# 04-PCIe_JTAG.net
KiCad netlist of a schematic drawn in Altium Designer
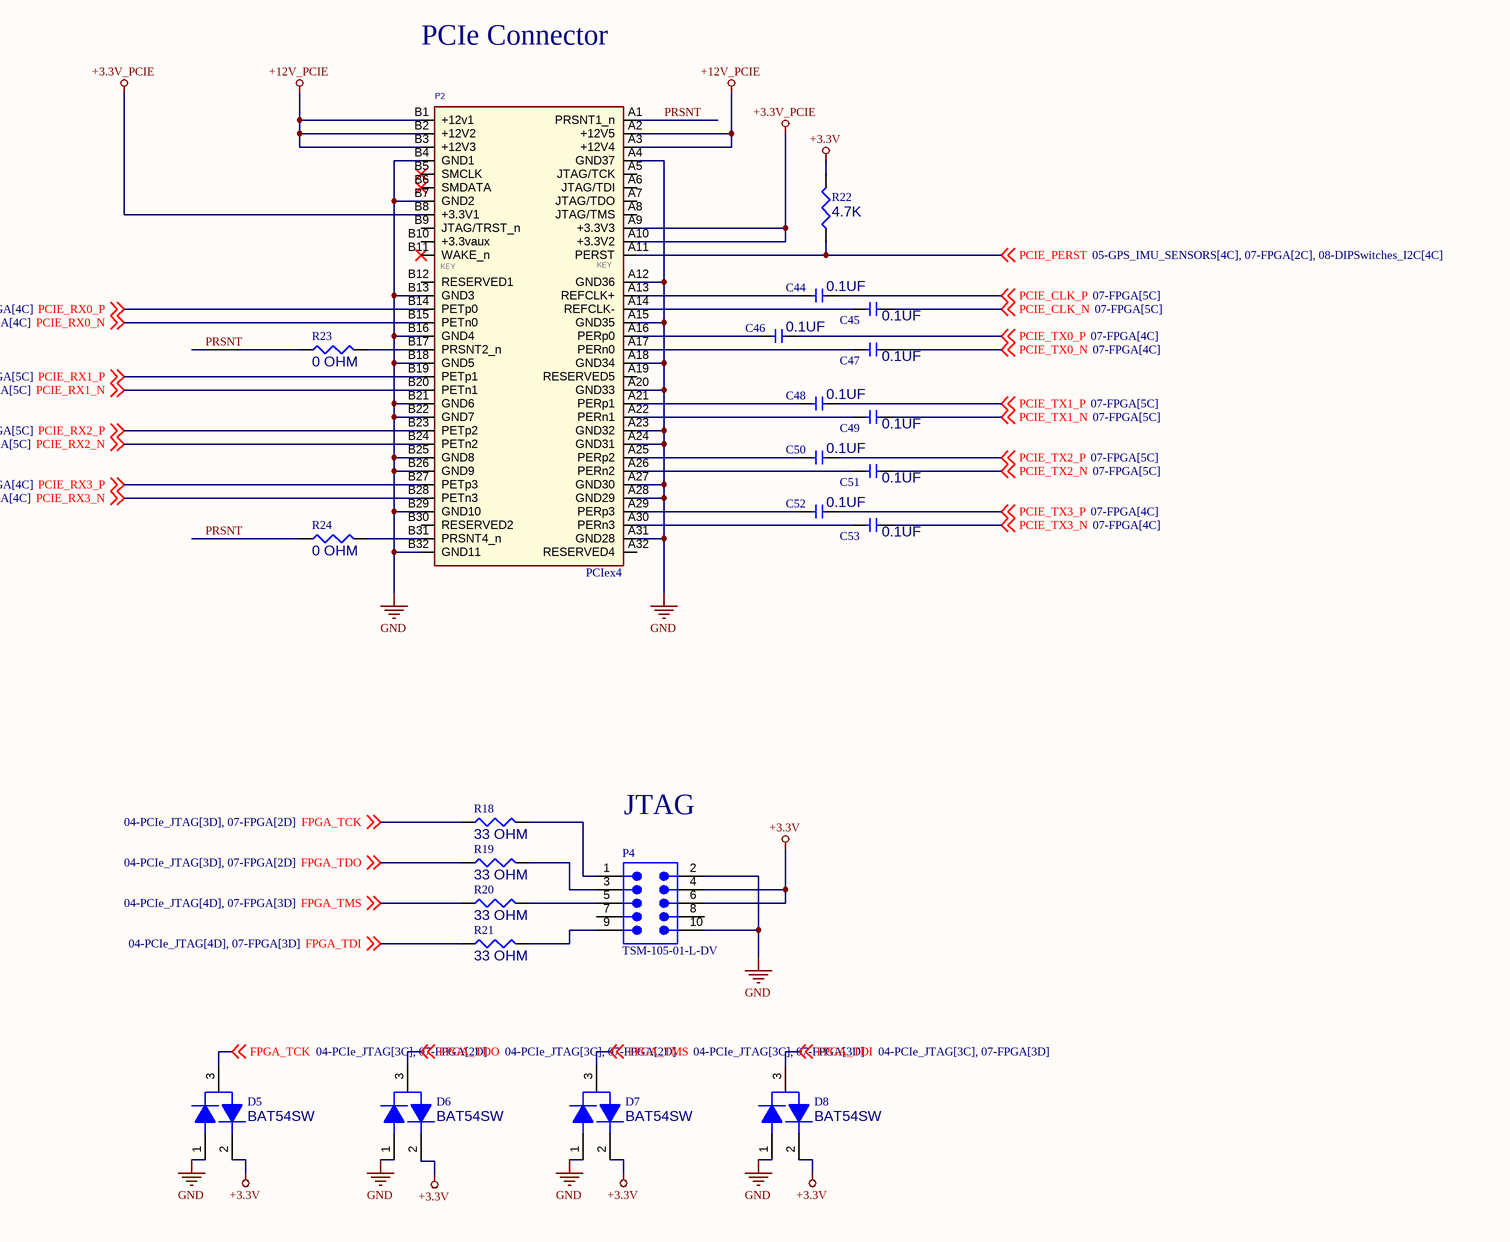
[diagram p0: 04-PCIe_JTAG.SchDoc]

(export (version "E")
  (design (tool "Eeschema 10.0.6"))
  (components
    (comp (ref "C44")
      (value "0.1UF")
      (footprint "CAPC1005X06N")
      (description "CAP, CER, 0.1UF, 50V, 10%, X7R, AEC-Q200, 0402")
      (fields
        (field (name "MFG PART NUM") "CGA2B3X7R1H104K050BB")
        (field (name "VALENTIUM PART NUM") "<VALENTIUM>")
      )
      (libsource (lib "Capacitors") (part "CAP_0402_0.1UF_50V"))
    )
    (comp (ref "C45")
      (value "0.1UF")
      (footprint "CAPC1005X06N")
      (description "CAP, CER, 0.1UF, 50V, 10%, X7R, AEC-Q200, 0402")
      (fields
        (field (name "MFG PART NUM") "CGA2B3X7R1H104K050BB")
        (field (name "VALENTIUM PART NUM") "<VALENTIUM>")
      )
      (libsource (lib "Capacitors") (part "CAP_0402_0.1UF_50V"))
    )
    (comp (ref "C46")
      (value "0.1UF")
      (footprint "CAPC1005X06N")
      (description "CAP, CER, 0.1UF, 50V, 10%, X7R, AEC-Q200, 0402")
      (fields
        (field (name "MFG PART NUM") "CGA2B3X7R1H104K050BB")
        (field (name "VALENTIUM PART NUM") "<VALENTIUM>")
      )
      (libsource (lib "Capacitors") (part "CAP_0402_0.1UF_50V"))
    )
    (comp (ref "C47")
      (value "0.1UF")
      (footprint "CAPC1005X06N")
      (description "CAP, CER, 0.1UF, 50V, 10%, X7R, AEC-Q200, 0402")
      (fields
        (field (name "MFG PART NUM") "CGA2B3X7R1H104K050BB")
        (field (name "VALENTIUM PART NUM") "<VALENTIUM>")
      )
      (libsource (lib "Capacitors") (part "CAP_0402_0.1UF_50V"))
    )
    (comp (ref "C48")
      (value "0.1UF")
      (footprint "CAPC1005X06N")
      (description "CAP, CER, 0.1UF, 50V, 10%, X7R, AEC-Q200, 0402")
      (fields
        (field (name "MFG PART NUM") "CGA2B3X7R1H104K050BB")
        (field (name "VALENTIUM PART NUM") "<VALENTIUM>")
      )
      (libsource (lib "Capacitors") (part "CAP_0402_0.1UF_50V"))
    )
    (comp (ref "C49")
      (value "0.1UF")
      (footprint "CAPC1005X06N")
      (description "CAP, CER, 0.1UF, 50V, 10%, X7R, AEC-Q200, 0402")
      (fields
        (field (name "MFG PART NUM") "CGA2B3X7R1H104K050BB")
        (field (name "VALENTIUM PART NUM") "<VALENTIUM>")
      )
      (libsource (lib "Capacitors") (part "CAP_0402_0.1UF_50V"))
    )
    (comp (ref "C50")
      (value "0.1UF")
      (footprint "CAPC1005X06N")
      (description "CAP, CER, 0.1UF, 50V, 10%, X7R, AEC-Q200, 0402")
      (fields
        (field (name "MFG PART NUM") "CGA2B3X7R1H104K050BB")
        (field (name "VALENTIUM PART NUM") "<VALENTIUM>")
      )
      (libsource (lib "Capacitors") (part "CAP_0402_0.1UF_50V"))
    )
    (comp (ref "C51")
      (value "0.1UF")
      (footprint "CAPC1005X06N")
      (description "CAP, CER, 0.1UF, 50V, 10%, X7R, AEC-Q200, 0402")
      (fields
        (field (name "MFG PART NUM") "CGA2B3X7R1H104K050BB")
        (field (name "VALENTIUM PART NUM") "<VALENTIUM>")
      )
      (libsource (lib "Capacitors") (part "CAP_0402_0.1UF_50V"))
    )
    (comp (ref "C52")
      (value "0.1UF")
      (footprint "CAPC1005X06N")
      (description "CAP, CER, 0.1UF, 50V, 10%, X7R, AEC-Q200, 0402")
      (fields
        (field (name "MFG PART NUM") "CGA2B3X7R1H104K050BB")
        (field (name "VALENTIUM PART NUM") "<VALENTIUM>")
      )
      (libsource (lib "Capacitors") (part "CAP_0402_0.1UF_50V"))
    )
    (comp (ref "C53")
      (value "0.1UF")
      (footprint "CAPC1005X06N")
      (description "CAP, CER, 0.1UF, 50V, 10%, X7R, AEC-Q200, 0402")
      (fields
        (field (name "MFG PART NUM") "CGA2B3X7R1H104K050BB")
        (field (name "VALENTIUM PART NUM") "<VALENTIUM>")
      )
      (libsource (lib "Capacitors") (part "CAP_0402_0.1UF_50V"))
    )
    (comp (ref "D5")
      (value "BAT54SW")
      (footprint "SOT65P210X110-3N")
      (description "DIO, SCHOTTKY, BAT54S, DUAL SERIES, 30V, 200MA, SC-70")
      (fields (field (name "MFG PART NUM") "BAT54SWQ-7-F") (field (name "VALENTIUM PART NUM") "<VALENTIUM>"))
      (libsource (lib "Passives") (part "BAT54SW"))
    )
    (comp (ref "D6")
      (value "BAT54SW")
      (footprint "SOT65P210X110-3N")
      (description "DIO, SCHOTTKY, BAT54S, DUAL SERIES, 30V, 200MA, SC-70")
      (fields (field (name "MFG PART NUM") "BAT54SWQ-7-F") (field (name "VALENTIUM PART NUM") "<VALENTIUM>"))
      (libsource (lib "Passives") (part "BAT54SW"))
    )
    (comp (ref "D7")
      (value "BAT54SW")
      (footprint "SOT65P210X110-3N")
      (description "DIO, SCHOTTKY, BAT54S, DUAL SERIES, 30V, 200MA, SC-70")
      (fields (field (name "MFG PART NUM") "BAT54SWQ-7-F") (field (name "VALENTIUM PART NUM") "<VALENTIUM>"))
      (libsource (lib "Passives") (part "BAT54SW"))
    )
    (comp (ref "D8")
      (value "BAT54SW")
      (footprint "SOT65P210X110-3N")
      (description "DIO, SCHOTTKY, BAT54S, DUAL SERIES, 30V, 200MA, SC-70")
      (fields (field (name "MFG PART NUM") "BAT54SWQ-7-F") (field (name "VALENTIUM PART NUM") "<VALENTIUM>"))
      (libsource (lib "Passives") (part "BAT54SW"))
    )
    (comp (ref "P2")
      (value "PCIex4")
      (footprint "PCIE_4LANE_EDGE")
      (description "PCIE x4 Edge Connector,OrCAD Symbol,NC")
      (fields (field (name "PART NUMBER") "451") (field (name "MANUFACTURER") "NA"))
      (libsource (lib "Connectors") (part "PCIex4"))
    )
    (comp (ref "P4")
      (value "TSM-105-01-L-DV")
      (footprint "SMTC-TSM-105-01-X-DV")
      (fields (field (name "MANUFACTURER") "Samtec"))
      (libsource (lib "Altium Content Vault") (part "SMTC-TSM-105-01-X-X"))
    )
    (comp (ref "R18")
      (value "33 OHM")
      (footprint "RESC2012X50N")
      (description "RES, 33 OHM, 1%, 1/8W, TF, 0805")
      (fields
        (field (name "MFG PART NUM") "CRCW080533R0FKEA")
        (field (name "VELENTIUM PART NUM") "<VELENTIUM>")
      )
      (libsource (lib "Resistors") (part "RES_0805_33"))
    )
    (comp (ref "R19")
      (value "33 OHM")
      (footprint "RESC2012X50N")
      (description "RES, 33 OHM, 1%, 1/8W, TF, 0805")
      (fields
        (field (name "MFG PART NUM") "CRCW080533R0FKEA")
        (field (name "VELENTIUM PART NUM") "<VELENTIUM>")
      )
      (libsource (lib "Resistors") (part "RES_0805_33"))
    )
    (comp (ref "R20")
      (value "33 OHM")
      (footprint "RESC2012X50N")
      (description "RES, 33 OHM, 1%, 1/8W, TF, 0805")
      (fields
        (field (name "MFG PART NUM") "CRCW080533R0FKEA")
        (field (name "VELENTIUM PART NUM") "<VELENTIUM>")
      )
      (libsource (lib "Resistors") (part "RES_0805_33"))
    )
    (comp (ref "R21")
      (value "33 OHM")
      (footprint "RESC2012X50N")
      (description "RES, 33 OHM, 1%, 1/8W, TF, 0805")
      (fields
        (field (name "MFG PART NUM") "CRCW080533R0FKEA")
        (field (name "VELENTIUM PART NUM") "<VELENTIUM>")
      )
      (libsource (lib "Resistors") (part "RES_0805_33"))
    )
    (comp (ref "R22")
      (value "4.7K")
      (footprint "RESC1608X50N")
      (description "RES, 4.7K, 1%, 1/10W, TF, 0603")
      (fields (field (name "MFG PART NUM") "ERJ-3EKF4701V") (field (name "VELENTIUM PART NUM") "<VELENTIUM>"))
      (libsource (lib "Resistors") (part "RES_0603_4.7K"))
    )
    (comp (ref "R23")
      (value "0 OHM")
      (footprint "RESC1005X04N")
      (description "RES, 0. OHM, 1%, 1/16W, TF, AEC-Q200, 0402")
      (fields (field (name "MFG PART NUM") "ERJ-2GE0R00X") (field (name "VELENTIUM PART NUM") "<VELENTIUM>"))
      (libsource (lib "Resistors") (part "RES_0402_0"))
    )
    (comp (ref "R24")
      (value "0 OHM")
      (footprint "RESC1005X04N")
      (description "RES, 0. OHM, 1%, 1/16W, TF, AEC-Q200, 0402")
      (fields (field (name "MFG PART NUM") "ERJ-2GE0R00X") (field (name "VELENTIUM PART NUM") "<VELENTIUM>"))
      (libsource (lib "Resistors") (part "RES_0402_0"))
    )
  )
  (nets
    (net (code "1") (name "+3.3V") (class "Default")
      (node (ref "D5") (pin "2") (pinfunction "2_2") (pintype "passive"))
      (node (ref "D6") (pin "2") (pinfunction "2_2") (pintype "passive"))
      (node (ref "D7") (pin "2") (pinfunction "2_2") (pintype "passive"))
      (node (ref "D8") (pin "2") (pinfunction "2_2") (pintype "passive"))
      (node (ref "P4") (pin "4") (pinfunction "4_4") (pintype "passive"))
      (node (ref "P4") (pin "6") (pinfunction "6_6") (pintype "passive"))
      (node (ref "R22") (pin "2") (pinfunction "2_2") (pintype "passive"))
    )
    (net (code "2") (name "+3.3V_PCIE") (class "Default")
      (node (ref "P2") (pin "A10") (pinfunction "+3.3V2_A10") (pintype "passive"))
      (node (ref "P2") (pin "A9") (pinfunction "+3.3V3_A9") (pintype "passive"))
      (node (ref "P2") (pin "B8") (pinfunction "+3.3V1_B8") (pintype "power_in"))
    )
    (net (code "3") (name "+12V_PCIE") (class "Default")
      (node (ref "P2") (pin "A2") (pinfunction "+12V5_A2") (pintype "passive"))
      (node (ref "P2") (pin "A3") (pinfunction "+12V4_A3") (pintype "passive"))
      (node (ref "P2") (pin "B1") (pinfunction "+12v1_B1") (pintype "power_in"))
      (node (ref "P2") (pin "B2") (pinfunction "+12V2_B2") (pintype "power_in"))
      (node (ref "P2") (pin "B3") (pinfunction "+12V3_B3") (pintype "power_in"))
    )
    (net (code "4") (name "/PRSNT") (class "Default")
      (node (ref "P2") (pin "A1") (pinfunction "PRSNT1_n_A1") (pintype "passive"))
      (node (ref "R23") (pin "1") (pinfunction "1_1") (pintype "passive"))
      (node (ref "R24") (pin "1") (pinfunction "1_1") (pintype "passive"))
    )
    (net (code "5") (name "FPGA_TCK") (class "Default")
      (node (ref "D5") (pin "3") (pinfunction "3_3") (pintype "passive"))
      (node (ref "R18") (pin "1") (pinfunction "1_1") (pintype "passive"))
    )
    (net (code "6") (name "FPGA_TDI") (class "Default")
      (node (ref "D8") (pin "3") (pinfunction "3_3") (pintype "passive"))
      (node (ref "R21") (pin "1") (pinfunction "1_1") (pintype "passive"))
    )
    (net (code "7") (name "FPGA_TDO") (class "Default")
      (node (ref "D6") (pin "3") (pinfunction "3_3") (pintype "passive"))
      (node (ref "R19") (pin "1") (pinfunction "1_1") (pintype "passive"))
    )
    (net (code "8") (name "FPGA_TMS") (class "Default")
      (node (ref "D7") (pin "3") (pinfunction "3_3") (pintype "passive"))
      (node (ref "R20") (pin "1") (pinfunction "1_1") (pintype "passive"))
    )
    (net (code "9") (name "GND") (class "Default")
      (node (ref "D5") (pin "1") (pinfunction "1_1") (pintype "passive"))
      (node (ref "D6") (pin "1") (pinfunction "1_1") (pintype "passive"))
      (node (ref "D7") (pin "1") (pinfunction "1_1") (pintype "passive"))
      (node (ref "D8") (pin "1") (pinfunction "1_1") (pintype "passive"))
      (node (ref "P2") (pin "A12") (pinfunction "GND36_A12") (pintype "power_in"))
      (node (ref "P2") (pin "A15") (pinfunction "GND35_A15") (pintype "power_in"))
      (node (ref "P2") (pin "A18") (pinfunction "GND34_A18") (pintype "power_in"))
      (node (ref "P2") (pin "A20") (pinfunction "GND33_A20") (pintype "power_in"))
      (node (ref "P2") (pin "A23") (pinfunction "GND32_A23") (pintype "power_in"))
      (node (ref "P2") (pin "A24") (pinfunction "GND31_A24") (pintype "power_in"))
      (node (ref "P2") (pin "A27") (pinfunction "GND30_A27") (pintype "power_in"))
      (node (ref "P2") (pin "A28") (pinfunction "GND29_A28") (pintype "power_in"))
      (node (ref "P2") (pin "A31") (pinfunction "GND28_A31") (pintype "power_in"))
      (node (ref "P2") (pin "A4") (pinfunction "GND37_A4") (pintype "power_in"))
      (node (ref "P2") (pin "B13") (pinfunction "GND3_B13") (pintype "power_in"))
      (node (ref "P2") (pin "B16") (pinfunction "GND4_B16") (pintype "power_in"))
      (node (ref "P2") (pin "B18") (pinfunction "GND5_B18") (pintype "power_in"))
      (node (ref "P2") (pin "B21") (pinfunction "GND6_B21") (pintype "power_in"))
      (node (ref "P2") (pin "B22") (pinfunction "GND7_B22") (pintype "power_in"))
      (node (ref "P2") (pin "B25") (pinfunction "GND8_B25") (pintype "power_in"))
      (node (ref "P2") (pin "B26") (pinfunction "GND9_B26") (pintype "power_in"))
      (node (ref "P2") (pin "B29") (pinfunction "GND10_B29") (pintype "power_in"))
      (node (ref "P2") (pin "B32") (pinfunction "GND11_B32") (pintype "power_in"))
      (node (ref "P2") (pin "B4") (pinfunction "GND1_B4") (pintype "power_in"))
      (node (ref "P2") (pin "B7") (pinfunction "GND2_B7") (pintype "power_in"))
      (node (ref "P4") (pin "10") (pinfunction "10_10") (pintype "passive"))
      (node (ref "P4") (pin "2") (pinfunction "2_2") (pintype "passive"))
    )
    (net (code "10") (name "Net-(P2-PERn0)") (class "Default")
      (node (ref "C47") (pin "1") (pinfunction "1_1") (pintype "passive"))
      (node (ref "P2") (pin "A17") (pinfunction "PERn0_A17") (pintype "passive"))
    )
    (net (code "11") (name "Net-(P2-PERn1)") (class "Default")
      (node (ref "C49") (pin "1") (pinfunction "1_1") (pintype "passive"))
      (node (ref "P2") (pin "A22") (pinfunction "PERn1_A22") (pintype "passive"))
    )
    (net (code "12") (name "Net-(P2-PERn2)") (class "Default")
      (node (ref "C51") (pin "1") (pinfunction "1_1") (pintype "passive"))
      (node (ref "P2") (pin "A26") (pinfunction "PERn2_A26") (pintype "passive"))
    )
    (net (code "13") (name "Net-(P2-PERn3)") (class "Default")
      (node (ref "C53") (pin "1") (pinfunction "1_1") (pintype "passive"))
      (node (ref "P2") (pin "A30") (pinfunction "PERn3_A30") (pintype "passive"))
    )
    (net (code "14") (name "Net-(P2-PERp0)") (class "Default")
      (node (ref "C46") (pin "1") (pinfunction "1_1") (pintype "passive"))
      (node (ref "P2") (pin "A16") (pinfunction "PERp0_A16") (pintype "passive"))
    )
    (net (code "15") (name "Net-(P2-PERp1)") (class "Default")
      (node (ref "C48") (pin "1") (pinfunction "1_1") (pintype "passive"))
      (node (ref "P2") (pin "A21") (pinfunction "PERp1_A21") (pintype "passive"))
    )
    (net (code "16") (name "Net-(P2-PERp2)") (class "Default")
      (node (ref "C50") (pin "1") (pinfunction "1_1") (pintype "passive"))
      (node (ref "P2") (pin "A25") (pinfunction "PERp2_A25") (pintype "passive"))
    )
    (net (code "17") (name "Net-(P2-PERp3)") (class "Default")
      (node (ref "C52") (pin "1") (pinfunction "1_1") (pintype "passive"))
      (node (ref "P2") (pin "A29") (pinfunction "PERp3_A29") (pintype "passive"))
    )
    (net (code "18") (name "Net-(P2-PRSNT2_n)") (class "Default")
      (node (ref "P2") (pin "B17") (pinfunction "PRSNT2_n_B17") (pintype "passive"))
      (node (ref "R23") (pin "2") (pinfunction "2_2") (pintype "passive"))
    )
    (net (code "19") (name "Net-(P2-PRSNT4_n)") (class "Default")
      (node (ref "P2") (pin "B31") (pinfunction "PRSNT4_n_B31") (pintype "passive"))
      (node (ref "R24") (pin "2") (pinfunction "2_2") (pintype "passive"))
    )
    (net (code "20") (name "Net-(P2-REFCLK+)") (class "Default")
      (node (ref "C44") (pin "1") (pinfunction "1_1") (pintype "passive"))
      (node (ref "P2") (pin "A13") (pinfunction "REFCLK+_A13") (pintype "passive"))
    )
    (net (code "21") (name "Net-(P2-REFCLK-)") (class "Default")
      (node (ref "C45") (pin "1") (pinfunction "1_1") (pintype "passive"))
      (node (ref "P2") (pin "A14") (pinfunction "REFCLK-_A14") (pintype "passive"))
    )
    (net (code "22") (name "Net-(P4-Pad1)") (class "Default")
      (node (ref "P4") (pin "1") (pinfunction "1_1") (pintype "passive"))
      (node (ref "R18") (pin "2") (pinfunction "2_2") (pintype "passive"))
    )
    (net (code "23") (name "Net-(P4-Pad3)") (class "Default")
      (node (ref "P4") (pin "3") (pinfunction "3_3") (pintype "passive"))
      (node (ref "R19") (pin "2") (pinfunction "2_2") (pintype "passive"))
    )
    (net (code "24") (name "Net-(P4-Pad5)") (class "Default")
      (node (ref "P4") (pin "5") (pinfunction "5_5") (pintype "passive"))
      (node (ref "R20") (pin "2") (pinfunction "2_2") (pintype "passive"))
    )
    (net (code "25") (name "Net-(P4-Pad9)") (class "Default")
      (node (ref "P4") (pin "9") (pinfunction "9_9") (pintype "passive"))
      (node (ref "R21") (pin "2") (pinfunction "2_2") (pintype "passive"))
    )
    (net (code "26") (name "PCIE_CLK_N") (class "Default")
      (node (ref "C45") (pin "2") (pinfunction "2_2") (pintype "passive"))
    )
    (net (code "27") (name "PCIE_CLK_P") (class "Default")
      (node (ref "C44") (pin "2") (pinfunction "2_2") (pintype "passive"))
    )
    (net (code "28") (name "PCIE_PERST") (class "Default")
      (node (ref "P2") (pin "A11") (pinfunction "PERST_A11") (pintype "passive"))
      (node (ref "R22") (pin "1") (pinfunction "1_1") (pintype "passive"))
    )
    (net (code "29") (name "PCIE_RX0_N") (class "Default")
      (node (ref "P2") (pin "B15") (pinfunction "PETn0_B15") (pintype "passive"))
    )
    (net (code "30") (name "PCIE_RX0_P") (class "Default")
      (node (ref "P2") (pin "B14") (pinfunction "PETp0_B14") (pintype "passive"))
    )
    (net (code "31") (name "PCIE_RX1_N") (class "Default")
      (node (ref "P2") (pin "B20") (pinfunction "PETn1_B20") (pintype "passive"))
    )
    (net (code "32") (name "PCIE_RX1_P") (class "Default")
      (node (ref "P2") (pin "B19") (pinfunction "PETp1_B19") (pintype "passive"))
    )
    (net (code "33") (name "PCIE_RX2_N") (class "Default")
      (node (ref "P2") (pin "B24") (pinfunction "PETn2_B24") (pintype "passive"))
    )
    (net (code "34") (name "PCIE_RX2_P") (class "Default")
      (node (ref "P2") (pin "B23") (pinfunction "PETp2_B23") (pintype "passive"))
    )
    (net (code "35") (name "PCIE_RX3_N") (class "Default")
      (node (ref "P2") (pin "B28") (pinfunction "PETn3_B28") (pintype "passive"))
    )
    (net (code "36") (name "PCIE_RX3_P") (class "Default")
      (node (ref "P2") (pin "B27") (pinfunction "PETp3_B27") (pintype "passive"))
    )
    (net (code "37") (name "PCIE_TX0_N") (class "Default")
      (node (ref "C47") (pin "2") (pinfunction "2_2") (pintype "passive"))
    )
    (net (code "38") (name "PCIE_TX0_P") (class "Default")
      (node (ref "C46") (pin "2") (pinfunction "2_2") (pintype "passive"))
    )
    (net (code "39") (name "PCIE_TX1_N") (class "Default")
      (node (ref "C49") (pin "2") (pinfunction "2_2") (pintype "passive"))
    )
    (net (code "40") (name "PCIE_TX1_P") (class "Default")
      (node (ref "C48") (pin "2") (pinfunction "2_2") (pintype "passive"))
    )
    (net (code "41") (name "PCIE_TX2_N") (class "Default")
      (node (ref "C51") (pin "2") (pinfunction "2_2") (pintype "passive"))
    )
    (net (code "42") (name "PCIE_TX2_P") (class "Default")
      (node (ref "C50") (pin "2") (pinfunction "2_2") (pintype "passive"))
    )
    (net (code "43") (name "PCIE_TX3_N") (class "Default")
      (node (ref "C53") (pin "2") (pinfunction "2_2") (pintype "passive"))
    )
    (net (code "44") (name "PCIE_TX3_P") (class "Default")
      (node (ref "C52") (pin "2") (pinfunction "2_2") (pintype "passive"))
    )
    (net (code "45") (name "unconnected-(P2-+3.3vaux-PadB10)") (class "Default")
      (node (ref "P2") (pin "B10") (pinfunction "+3.3vaux_B10") (pintype "passive"))
    )
    (net (code "46") (name "unconnected-(P2-JTAG{slash}TCK-PadA5)") (class "Default")
      (node (ref "P2") (pin "A5") (pinfunction "JTAG/TCK_A5") (pintype "passive"))
    )
    (net (code "47") (name "unconnected-(P2-JTAG{slash}TDI-PadA6)") (class "Default")
      (node (ref "P2") (pin "A6") (pinfunction "JTAG/TDI_A6") (pintype "passive"))
    )
    (net (code "48") (name "unconnected-(P2-JTAG{slash}TDO-PadA7)") (class "Default")
      (node (ref "P2") (pin "A7") (pinfunction "JTAG/TDO_A7") (pintype "passive"))
    )
    (net (code "49") (name "unconnected-(P2-JTAG{slash}TMS-PadA8)") (class "Default")
      (node (ref "P2") (pin "A8") (pinfunction "JTAG/TMS_A8") (pintype "passive"))
    )
    (net (code "50") (name "unconnected-(P2-JTAG{slash}TRST_n-PadB9)") (class "Default")
      (node (ref "P2") (pin "B9") (pinfunction "JTAG/TRST_n_B9") (pintype "passive"))
    )
    (net (code "51") (name "unconnected-(P2-RESERVED1-PadB12)") (class "Default")
      (node (ref "P2") (pin "B12") (pinfunction "RESERVED1_B12") (pintype "passive"))
    )
    (net (code "52") (name "unconnected-(P2-RESERVED2-PadB30)") (class "Default")
      (node (ref "P2") (pin "B30") (pinfunction "RESERVED2_B30") (pintype "passive"))
    )
    (net (code "53") (name "unconnected-(P2-RESERVED4-PadA32)") (class "Default")
      (node (ref "P2") (pin "A32") (pinfunction "RESERVED4_A32") (pintype "passive"))
    )
    (net (code "54") (name "unconnected-(P2-RESERVED5-PadA19)") (class "Default")
      (node (ref "P2") (pin "A19") (pinfunction "RESERVED5_A19") (pintype "passive"))
    )
    (net (code "55") (name "unconnected-(P2-SMCLK-PadB5)") (class "Default")
      (node (ref "P2") (pin "B5") (pinfunction "SMCLK_B5") (pintype "passive+no_connect"))
    )
    (net (code "56") (name "unconnected-(P2-SMDATA-PadB6)") (class "Default")
      (node (ref "P2") (pin "B6") (pinfunction "SMDATA_B6") (pintype "passive+no_connect"))
    )
    (net (code "57") (name "unconnected-(P2-WAKE_n-PadB11)") (class "Default")
      (node (ref "P2") (pin "B11") (pinfunction "WAKE_n_B11") (pintype "passive+no_connect"))
    )
    (net (code "58") (name "unconnected-(P4-Pad7)") (class "Default")
      (node (ref "P4") (pin "7") (pinfunction "7_7") (pintype "passive"))
    )
    (net (code "59") (name "unconnected-(P4-Pad8)") (class "Default")
      (node (ref "P4") (pin "8") (pinfunction "8_8") (pintype "passive"))
    )
  )
)
